# PressureConnector_2.net
KiCad netlist of a schematic drawn in Altium Designer
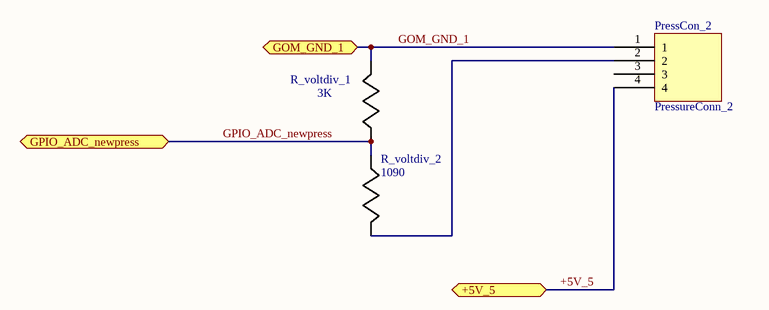
[diagram p0: PressureConnector_2.SchDoc]

(export (version "E")
  (design (tool "Eeschema 10.0.6"))
  (components
    (comp (ref "PressCon_2")
      (value "PressureConn_2")
      (footprint "PressCon_2")
      (libsource (lib "UmbilicalBoardV2") (part "PressureConn_2"))
    )
    (comp (ref "R_voltdiv_1")
      (value "3K")
      (footprint "0402")
      (description "Imported")
      (fields (field (name "MANUFACTURER_PART_NUMBER") "CRCW040210R0FKED"))
      (libsource (lib "2016-03-26_18-23-46") (part "CRCW040210R0FKED"))
    )
    (comp (ref "R_voltdiv_2")
      (value "1090")
      (footprint "0402")
      (description "Imported")
      (fields (field (name "MANUFACTURER_PART_NUMBER") "CRCW040210R0FKED"))
      (libsource (lib "2016-03-26_18-23-46") (part "CRCW040210R0FKED"))
    )
  )
  (nets
    (net (code "1") (name "/+5V_5") (class "Default")
      (node (ref "PressCon_2") (pin "4") (pinfunction "4_4") (pintype "passive"))
    )
    (net (code "2") (name "/GOM_GND_1") (class "Default")
      (node (ref "PressCon_2") (pin "1") (pinfunction "1_1") (pintype "passive"))
      (node (ref "R_voltdiv_1") (pin "1") (pinfunction "1_1") (pintype "passive"))
    )
    (net (code "3") (name "/GPIO_ADC_newpress") (class "Default")
      (node (ref "R_voltdiv_1") (pin "2") (pinfunction "2_2") (pintype "passive"))
      (node (ref "R_voltdiv_2") (pin "2") (pinfunction "2_2") (pintype "passive"))
    )
    (net (code "4") (name "Net-(PressCon_2-Pad2)") (class "Default")
      (node (ref "PressCon_2") (pin "2") (pinfunction "2_2") (pintype "passive"))
      (node (ref "R_voltdiv_2") (pin "1") (pinfunction "1_1") (pintype "passive"))
    )
    (net (code "5") (name "unconnected-(PressCon_2-Pad3)") (class "Default")
      (node (ref "PressCon_2") (pin "3") (pinfunction "3_3") (pintype "passive"))
    )
  )
)
